# EFR32BG13_INTERCONNECTS.net
KiCad netlist of a schematic drawn in Altium Designer
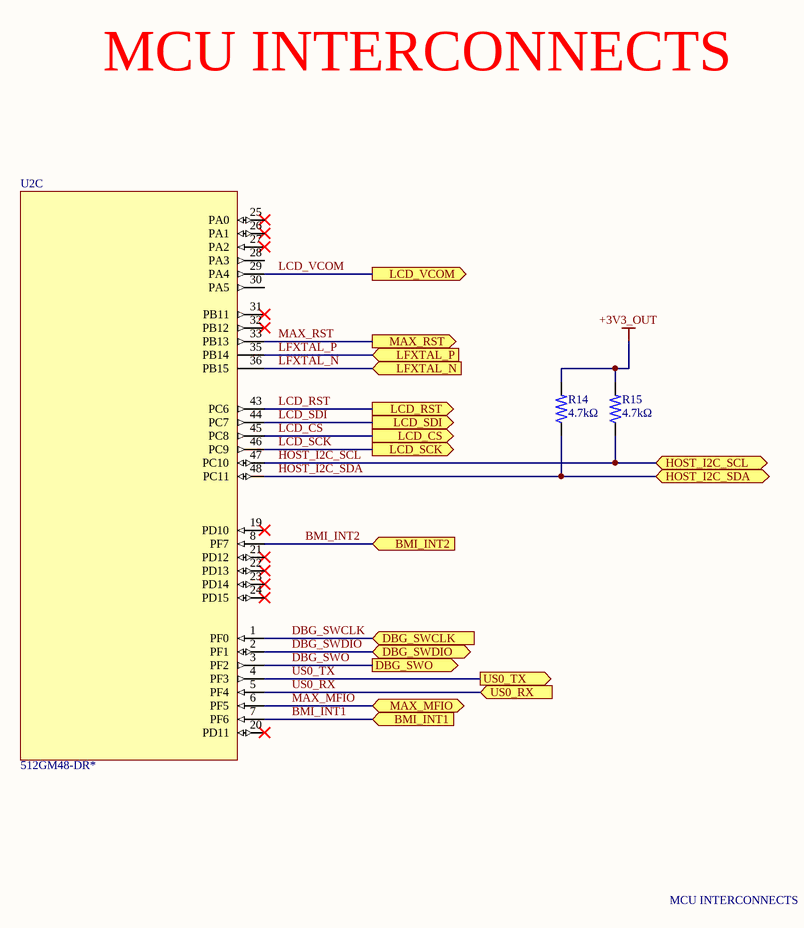
[diagram p0: EFR32BG13_INTERCONNECTS.SchDoc]

(export (version "E")
  (design (tool "Eeschema 10.0.6"))
  (components
    (comp (ref "R14")
      (value "4.7kΩ")
      (footprint "RES_0603_1608X06")
      (fields
        (field (name "MANUFACTURER") "Yageo")
        (field (name "MANUFACTURER PART NUMBER") "RC0603FR-074K7L")
        (field (name "TOLERANCE") "1%")
      )
      (libsource (lib "LPEDT_Components") (part "RES 4.7K 0603"))
    )
    (comp (ref "R15")
      (value "4.7kΩ")
      (footprint "RES_0603_1608X06")
      (fields
        (field (name "MANUFACTURER") "Yageo")
        (field (name "MANUFACTURER PART NUMBER") "RC0603FR-074K7L")
        (field (name "TOLERANCE") "1%")
      )
      (libsource (lib "LPEDT_Components") (part "RES 4.7K 0603"))
    )
    (comp (ref "U2")
      (value "512GM48-DR*")
      (footprint "QFN_48_7x7")
      (description "Blue Gecko QFN48 2.4 G 19 dB BLE/Proprietary 512 kB 64 kB(RAM) 31GPIO")
      (fields
        (field (name "MANUFACTURER") "Silicon Labs")
        (field (name "MANUFACTURER PART NUMBER") "EFR32BG13P732F512GM48-DR")
      )
      (libsource (lib "LPEDT_Components") (part "EFR32BG13P732F512GM48-DR"))
    )
  )
  (nets
    (net (code "1") (name "+3V3_OUT") (class "Default")
      (node (ref "R14") (pin "2") (pinfunction "2_2") (pintype "passive"))
      (node (ref "R15") (pin "2") (pinfunction "2_2") (pintype "passive"))
    )
    (net (code "2") (name "/BMI_INT1") (class "Default")
      (node (ref "U2") (pin "7") (pinfunction "PF6_7") (pintype "input"))
    )
    (net (code "3") (name "/BMI_INT2") (class "Default")
      (node (ref "U2") (pin "8") (pinfunction "PF7_8") (pintype "input"))
    )
    (net (code "4") (name "/DBG_SWCLK") (class "Default")
      (node (ref "U2") (pin "1") (pinfunction "PF0_1") (pintype "input"))
    )
    (net (code "5") (name "/DBG_SWDIO") (class "Default")
      (node (ref "U2") (pin "2") (pinfunction "PF1_2") (pintype "bidirectional"))
    )
    (net (code "6") (name "/DBG_SWO") (class "Default")
      (node (ref "U2") (pin "3") (pinfunction "PF2_3") (pintype "output"))
    )
    (net (code "7") (name "/HOST_I2C_SCL") (class "Default")
      (node (ref "R15") (pin "1") (pinfunction "1_1") (pintype "passive"))
      (node (ref "U2") (pin "47") (pinfunction "PC10_47") (pintype "bidirectional"))
    )
    (net (code "8") (name "/HOST_I2C_SDA") (class "Default")
      (node (ref "R14") (pin "1") (pinfunction "1_1") (pintype "passive"))
      (node (ref "U2") (pin "48") (pinfunction "PC11_48") (pintype "bidirectional"))
    )
    (net (code "9") (name "/LCD_CS") (class "Default")
      (node (ref "U2") (pin "45") (pinfunction "PC8_45") (pintype "output"))
    )
    (net (code "10") (name "/LCD_RST") (class "Default")
      (node (ref "U2") (pin "43") (pinfunction "PC6_43") (pintype "output"))
    )
    (net (code "11") (name "/LCD_SCK") (class "Default")
      (node (ref "U2") (pin "46") (pinfunction "PC9_46") (pintype "output"))
    )
    (net (code "12") (name "/LCD_SDI") (class "Default")
      (node (ref "U2") (pin "44") (pinfunction "PC7_44") (pintype "output"))
    )
    (net (code "13") (name "/LCD_VCOM") (class "Default")
      (node (ref "U2") (pin "29") (pinfunction "PA4_29") (pintype "output"))
    )
    (net (code "14") (name "/LFXTAL_N") (class "Default")
      (node (ref "U2") (pin "36") (pinfunction "PB15_36") (pintype "passive"))
    )
    (net (code "15") (name "/LFXTAL_P") (class "Default")
      (node (ref "U2") (pin "35") (pinfunction "PB14_35") (pintype "passive"))
    )
    (net (code "16") (name "/MAX_MFIO") (class "Default")
      (node (ref "U2") (pin "6") (pinfunction "PF5_6") (pintype "input"))
    )
    (net (code "17") (name "/MAX_RST") (class "Default")
      (node (ref "U2") (pin "33") (pinfunction "PB13_33") (pintype "output"))
    )
    (net (code "18") (name "/US0_RX") (class "Default")
      (node (ref "U2") (pin "5") (pinfunction "PF4_5") (pintype "input"))
    )
    (net (code "19") (name "/US0_TX") (class "Default")
      (node (ref "U2") (pin "4") (pinfunction "PF3_4") (pintype "output"))
    )
    (net (code "20") (name "unconnected-(U2C-PA0-Pad25)") (class "Default")
      (node (ref "U2") (pin "25") (pinfunction "PA0_25") (pintype "bidirectional+no_connect"))
    )
    (net (code "21") (name "unconnected-(U2C-PA1-Pad26)") (class "Default")
      (node (ref "U2") (pin "26") (pinfunction "PA1_26") (pintype "bidirectional+no_connect"))
    )
    (net (code "22") (name "unconnected-(U2C-PA2-Pad27)") (class "Default")
      (node (ref "U2") (pin "27") (pinfunction "PA2_27") (pintype "input+no_connect"))
    )
    (net (code "23") (name "unconnected-(U2C-PA3-Pad28)") (class "Default")
      (node (ref "U2") (pin "28") (pinfunction "PA3_28") (pintype "output"))
    )
    (net (code "24") (name "unconnected-(U2C-PA5-Pad30)") (class "Default")
      (node (ref "U2") (pin "30") (pinfunction "PA5_30") (pintype "output"))
    )
    (net (code "25") (name "unconnected-(U2C-PB11-Pad31)") (class "Default")
      (node (ref "U2") (pin "31") (pinfunction "PB11_31") (pintype "output+no_connect"))
    )
    (net (code "26") (name "unconnected-(U2C-PB12-Pad32)") (class "Default")
      (node (ref "U2") (pin "32") (pinfunction "PB12_32") (pintype "output+no_connect"))
    )
    (net (code "27") (name "unconnected-(U2C-PD10-Pad19)") (class "Default")
      (node (ref "U2") (pin "19") (pinfunction "PD10_19") (pintype "input+no_connect"))
    )
    (net (code "28") (name "unconnected-(U2C-PD11-Pad20)") (class "Default")
      (node (ref "U2") (pin "20") (pinfunction "PD11_20") (pintype "bidirectional+no_connect"))
    )
    (net (code "29") (name "unconnected-(U2C-PD12-Pad21)") (class "Default")
      (node (ref "U2") (pin "21") (pinfunction "PD12_21") (pintype "bidirectional+no_connect"))
    )
    (net (code "30") (name "unconnected-(U2C-PD13-Pad22)") (class "Default")
      (node (ref "U2") (pin "22") (pinfunction "PD13_22") (pintype "bidirectional+no_connect"))
    )
    (net (code "31") (name "unconnected-(U2C-PD14-Pad23)") (class "Default")
      (node (ref "U2") (pin "23") (pinfunction "PD14_23") (pintype "bidirectional+no_connect"))
    )
    (net (code "32") (name "unconnected-(U2C-PD15-Pad24)") (class "Default")
      (node (ref "U2") (pin "24") (pinfunction "PD15_24") (pintype "bidirectional+no_connect"))
    )
  )
)
